# hifi.net
KiCad netlist of a schematic drawn in EAGLE
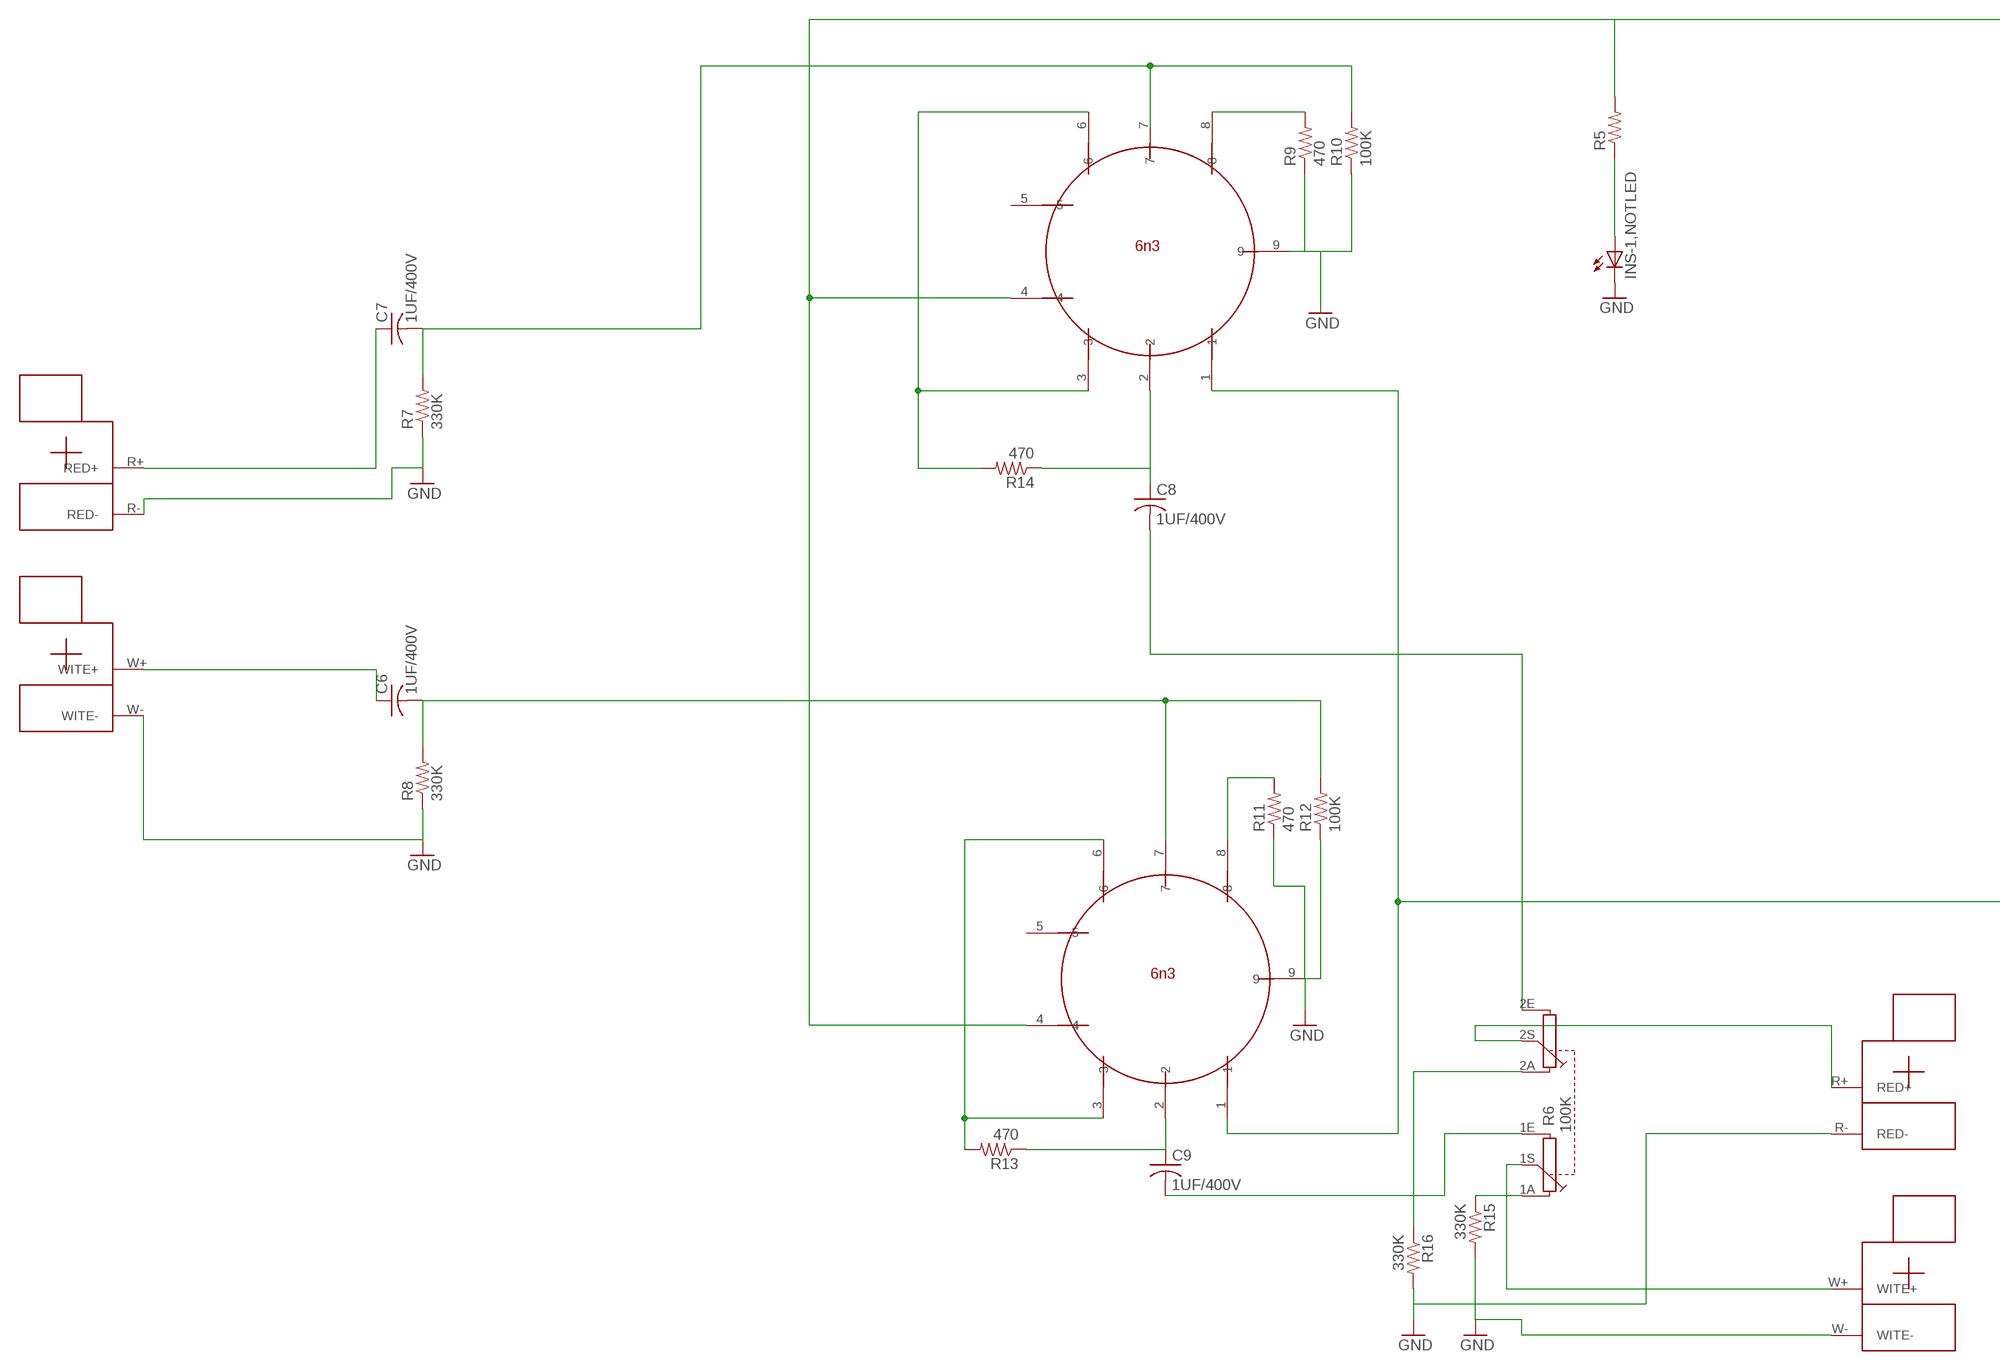
[diagram p0: schematic, sheet 1, part 1 of 2]
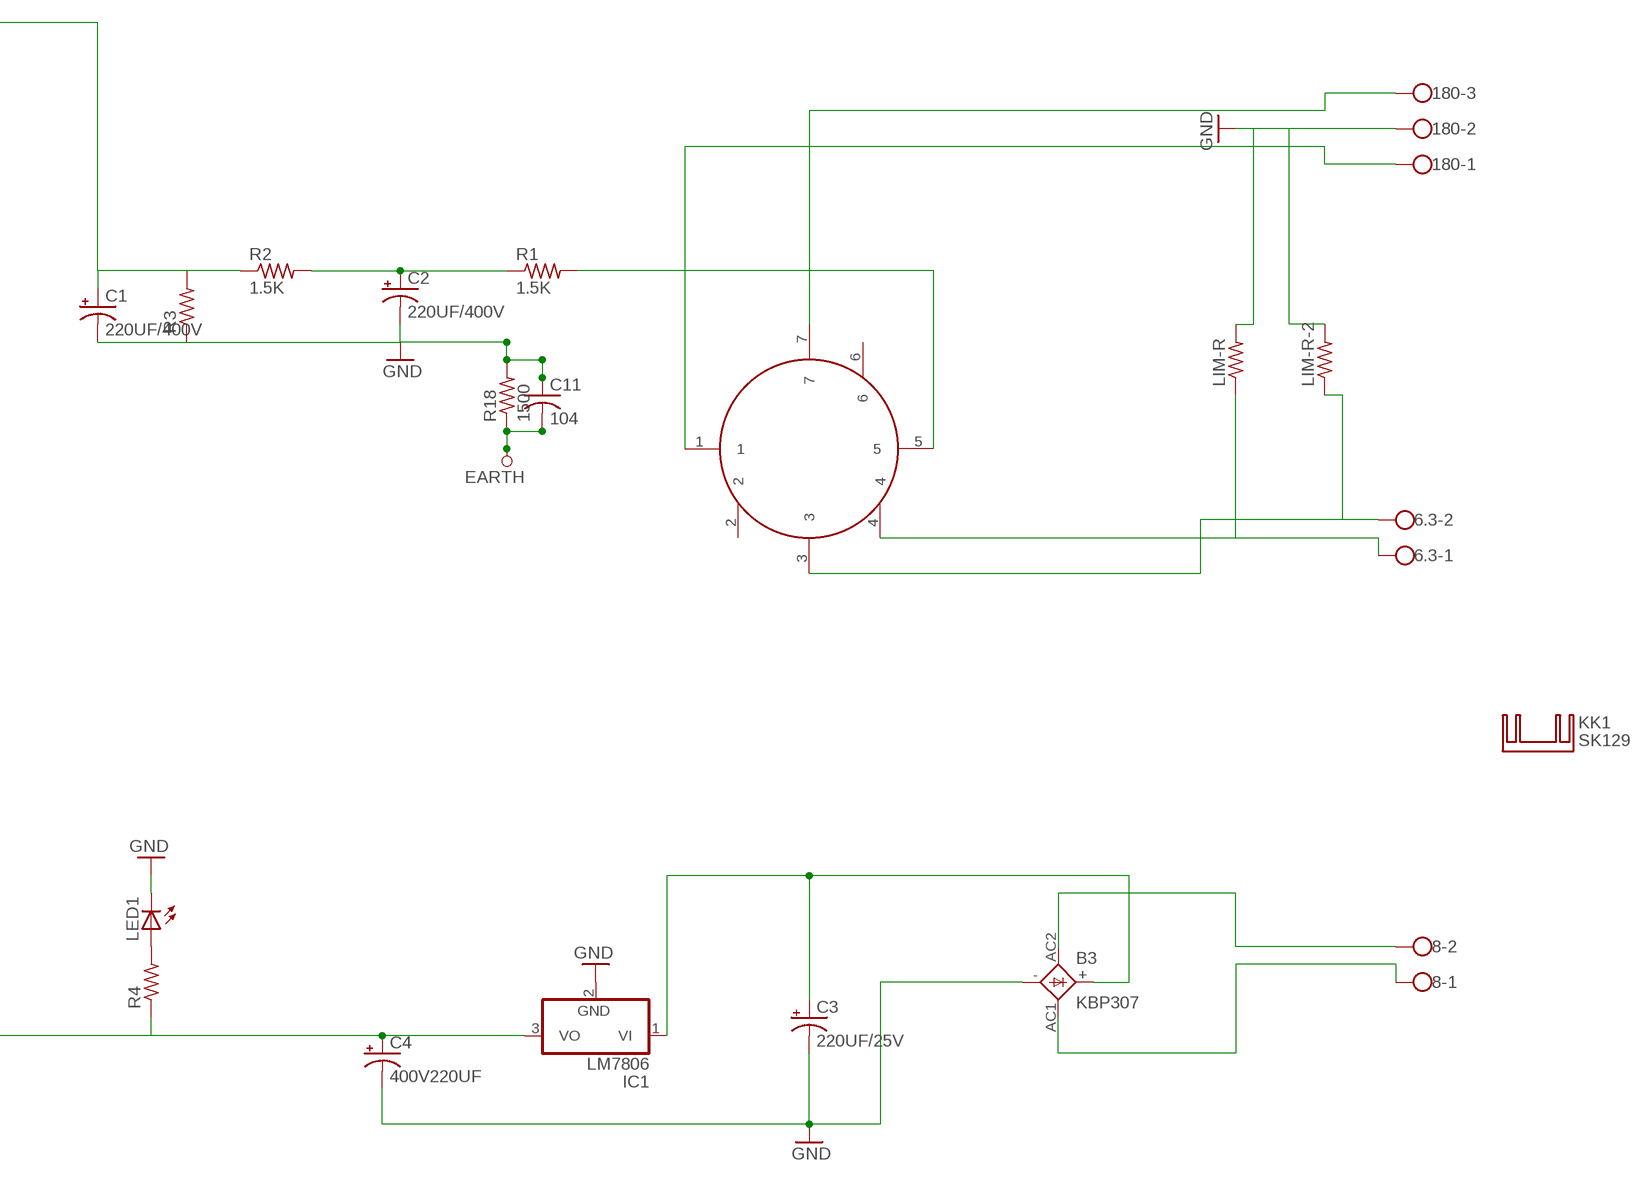
[diagram p1: schematic, sheet 1, part 2 of 2]

(export (version "E")
  (design (tool "Eeschema 10.0.6"))
  (components
    (comp (ref "6.3")
      (value "W237-102")
      (footprint "eagle-import:W237-102")
      (fields (field (name "MPN") "237-102"))
      (libsource (lib "eagle-import") (part "W237-102"))
    )
    (comp (ref "8")
      (value "W237-102")
      (footprint "eagle-import:W237-102")
      (fields (field (name "MPN") "237-102"))
      (libsource (lib "eagle-import") (part "W237-102"))
    )
    (comp (ref "180")
      (value "W237-103")
      (footprint "eagle-import:W237-103")
      (fields (field (name "MPN") "237-103"))
      (libsource (lib "eagle-import") (part "W237-103"))
    )
    (comp (ref "B3")
      (value "KBP307")
      (footprint "eagle-import:KBL")
      (libsource (lib "eagle-import") (part "KBL"))
    )
    (comp (ref "C1")
      (value "220UF/400V")
      (footprint "eagle-import:EB35D")
      (libsource (lib "eagle-import") (part "CPOL-USE10-35"))
    )
    (comp (ref "C2")
      (value "220UF/400V")
      (footprint "eagle-import:EB35D")
      (libsource (lib "eagle-import") (part "CPOL-USE10-35"))
    )
    (comp (ref "C3")
      (value "220UF/25V")
      (footprint "eagle-import:E3,5-10")
      (libsource (lib "eagle-import") (part "CPOL-USE3.5-10"))
    )
    (comp (ref "C4")
      (value "400V220UF")
      (footprint "eagle-import:EB30D")
      (libsource (lib "eagle-import") (part "CPOL-USE10-30"))
    )
    (comp (ref "C6")
      (value "1UF/400V")
      (footprint "eagle-import:C375-192X418")
      (libsource (lib "eagle-import") (part "C-US375-192X418"))
    )
    (comp (ref "C7")
      (value "1UF/400V")
      (footprint "eagle-import:C375-192X418")
      (libsource (lib "eagle-import") (part "C-US375-192X418"))
    )
    (comp (ref "C8")
      (value "1UF/400V")
      (footprint "eagle-import:C375-192X418")
      (libsource (lib "eagle-import") (part "C-US375-192X418"))
    )
    (comp (ref "C9")
      (value "1UF/400V")
      (footprint "eagle-import:C375-192X418")
      (libsource (lib "eagle-import") (part "C-US375-192X418"))
    )
    (comp (ref "C11")
      (value "104")
      (footprint "eagle-import:C075-052X106")
      (libsource (lib "eagle-import") (part "C-US075-052X106"))
    )
    (comp (ref "EARTH")
      (value "PAD_TERMINAL-4.1MMROUND")
      (footprint "eagle-import:PAD_ROUND_4.1MM")
      (libsource (lib "eagle-import") (part "PAD_TERMINAL-4.1MMROUND"))
    )
    (comp (ref "IC1")
      (value "LM7806")
      (footprint "eagle-import:TO220V")
      (libsource (lib "eagle-import") (part "78TV05"))
    )
    (comp (ref "INS-1,NOTLED")
      (value "LED5MM")
      (footprint "eagle-import:LED5MM")
      (libsource (lib "eagle-import") (part "LED5MM"))
    )
    (comp (ref "KK1")
      (value "SK129")
      (footprint "eagle-import:SK129-HOLE")
      (libsource (lib "eagle-import") (part "SK129"))
    )
    (comp (ref "LED1")
      (value "LED5MM")
      (footprint "eagle-import:LED5MM")
      (libsource (lib "eagle-import") (part "LED5MM"))
    )
    (comp (ref "LIM-R")
      (value "R-US_0207/10")
      (footprint "eagle-import:0207_10")
      (libsource (lib "eagle-import") (part "R-US_0207/10"))
    )
    (comp (ref "LIM-R-2")
      (value "R-US_0207/10")
      (footprint "eagle-import:0207_10")
      (libsource (lib "eagle-import") (part "R-US_0207/10"))
    )
    (comp (ref "R1")
      (value "1.5K")
      (footprint "eagle-import:0309_12")
      (libsource (lib "eagle-import") (part "R-US_0309/12"))
    )
    (comp (ref "R2")
      (value "1.5K")
      (footprint "eagle-import:0309_12")
      (libsource (lib "eagle-import") (part "R-US_0309/12"))
    )
    (comp (ref "R3")
      (value "R-US_0309/12")
      (footprint "eagle-import:0309_12")
      (libsource (lib "eagle-import") (part "R-US_0309/12"))
    )
    (comp (ref "R4")
      (value "R-US_0207/10")
      (footprint "eagle-import:0207_10")
      (libsource (lib "eagle-import") (part "R-US_0207/10"))
    )
    (comp (ref "R5")
      (value "R-US_0309/12")
      (footprint "eagle-import:0309_12")
      (libsource (lib "eagle-import") (part "R-US_0309/12"))
    )
    (comp (ref "R6")
      (value "100K")
      (footprint "eagle-import:PC16D")
      (libsource (lib "eagle-import") (part "PC16D"))
    )
    (comp (ref "R7")
      (value "330K")
      (footprint "eagle-import:0207_10")
      (libsource (lib "eagle-import") (part "R-US_0207/10"))
    )
    (comp (ref "R8")
      (value "330K")
      (footprint "eagle-import:0207_10")
      (libsource (lib "eagle-import") (part "R-US_0207/10"))
    )
    (comp (ref "R9")
      (value "470")
      (footprint "eagle-import:0207_10")
      (libsource (lib "eagle-import") (part "R-US_0207/10"))
    )
    (comp (ref "R10")
      (value "100K")
      (footprint "eagle-import:0207_10")
      (libsource (lib "eagle-import") (part "R-US_0207/10"))
    )
    (comp (ref "R11")
      (value "470")
      (footprint "eagle-import:0207_10")
      (libsource (lib "eagle-import") (part "R-US_0207/10"))
    )
    (comp (ref "R12")
      (value "100K")
      (footprint "eagle-import:0207_10")
      (libsource (lib "eagle-import") (part "R-US_0207/10"))
    )
    (comp (ref "R13")
      (value "470")
      (footprint "eagle-import:0207_10")
      (libsource (lib "eagle-import") (part "R-US_0207/10"))
    )
    (comp (ref "R14")
      (value "470")
      (footprint "eagle-import:0207_10")
      (libsource (lib "eagle-import") (part "R-US_0207/10"))
    )
    (comp (ref "R15")
      (value "330K")
      (footprint "eagle-import:0207_10")
      (libsource (lib "eagle-import") (part "R-US_0207/10"))
    )
    (comp (ref "R16")
      (value "330K")
      (footprint "eagle-import:0207_10")
      (libsource (lib "eagle-import") (part "R-US_0207/10"))
    )
    (comp (ref "R18")
      (value "1500")
      (footprint "eagle-import:0309_12")
      (libsource (lib "eagle-import") (part "R-US_0309/12"))
    )
    (comp (ref "U$1")
      (value "6Z4-SIMPLE")
      (footprint "eagle-import:MINI_P7")
      (libsource (lib "eagle-import") (part "6Z4-SIMPLE"))
    )
    (comp (ref "U$2")
      (value "6N3-SIMPLE")
      (footprint "eagle-import:NOVAL")
      (libsource (lib "eagle-import") (part "6N3-SIMPLE"))
    )
    (comp (ref "U$3")
      (value "6N3-SIMPLE")
      (footprint "eagle-import:NOVAL")
      (libsource (lib "eagle-import") (part "6N3-SIMPLE"))
    )
    (comp (ref "U$4")
      (value "RCANEW")
      (footprint "eagle-import:RCA")
      (libsource (lib "eagle-import") (part "RCANEW"))
    )
    (comp (ref "U$5")
      (value "RCANEW")
      (footprint "eagle-import:RCA")
      (libsource (lib "eagle-import") (part "RCANEW"))
    )
  )
  (nets
    (net (code "1") (name "GND") (class "Default")
      (node (ref "180") (pin "2") (pinfunction "KL_2") (pintype "passive"))
      (node (ref "B3") (pin "-") (pinfunction "-_-") (pintype "passive"))
      (node (ref "C1") (pin "-") (pinfunction "-_-") (pintype "passive"))
      (node (ref "C11") (pin "1") (pinfunction "1_1") (pintype "passive"))
      (node (ref "C2") (pin "-") (pinfunction "-_-") (pintype "passive"))
      (node (ref "C3") (pin "-") (pinfunction "-_-") (pintype "passive"))
      (node (ref "C4") (pin "-") (pinfunction "-_-") (pintype "passive"))
      (node (ref "IC1") (pin "2") (pinfunction "GND_2") (pintype "passive"))
      (node (ref "INS-1,NOTLED") (pin "K") (pinfunction "C_K") (pintype "passive"))
      (node (ref "LED1") (pin "K") (pinfunction "C_K") (pintype "passive"))
      (node (ref "LIM-R") (pin "2") (pinfunction "2_2") (pintype "passive"))
      (node (ref "LIM-R-2") (pin "2") (pinfunction "2_2") (pintype "passive"))
      (node (ref "R11") (pin "1") (pinfunction "1_1") (pintype "passive"))
      (node (ref "R12") (pin "1") (pinfunction "1_1") (pintype "passive"))
      (node (ref "R15") (pin "2") (pinfunction "2_2") (pintype "passive"))
      (node (ref "R16") (pin "2") (pinfunction "2_2") (pintype "passive"))
      (node (ref "R18") (pin "2") (pinfunction "2_2") (pintype "passive"))
      (node (ref "R3") (pin "1") (pinfunction "1_1") (pintype "passive"))
      (node (ref "R7") (pin "1") (pinfunction "1_1") (pintype "passive"))
      (node (ref "R8") (pin "1") (pinfunction "1_1") (pintype "passive"))
      (node (ref "U$3") (pin "9") (pinfunction "9_9") (pintype "bidirectional"))
      (node (ref "U$4") (pin "R-") (pinfunction "RED-_R-") (pintype "bidirectional"))
      (node (ref "U$4") (pin "W-") (pinfunction "WITE-_W-") (pintype "bidirectional"))
      (node (ref "U$5") (pin "R-") (pinfunction "RED-_R-") (pintype "bidirectional"))
      (node (ref "U$5") (pin "W-") (pinfunction "WITE-_W-") (pintype "bidirectional"))
    )
    (net (code "2") (name "Net-(6.3A-KL)") (class "Default")
      (node (ref "6.3") (pin "1") (pinfunction "KL_1") (pintype "passive"))
      (node (ref "LIM-R") (pin "1") (pinfunction "1_1") (pintype "passive"))
      (node (ref "U$1") (pin "4") (pinfunction "4_4") (pintype "bidirectional"))
    )
    (net (code "3") (name "Net-(6.3B-KL)") (class "Default")
      (node (ref "6.3") (pin "2") (pinfunction "KL_2") (pintype "passive"))
      (node (ref "LIM-R-2") (pin "1") (pinfunction "1_1") (pintype "passive"))
      (node (ref "U$1") (pin "3") (pinfunction "3_3") (pintype "bidirectional"))
    )
    (net (code "4") (name "Net-(8A-KL)") (class "Default")
      (node (ref "8") (pin "1") (pinfunction "KL_1") (pintype "passive"))
      (node (ref "B3") (pin "AC1") (pinfunction "AC2_AC1") (pintype "passive"))
    )
    (net (code "5") (name "Net-(8B-KL)") (class "Default")
      (node (ref "8") (pin "2") (pinfunction "KL_2") (pintype "passive"))
      (node (ref "B3") (pin "AC2") (pinfunction "AC1_AC2") (pintype "passive"))
    )
    (net (code "6") (name "Net-(180A-KL)") (class "Default")
      (node (ref "180") (pin "1") (pinfunction "KL_1") (pintype "passive"))
      (node (ref "U$1") (pin "1") (pinfunction "1_1") (pintype "bidirectional"))
    )
    (net (code "7") (name "Net-(180C-KL)") (class "Default")
      (node (ref "180") (pin "3") (pinfunction "KL_3") (pintype "passive"))
      (node (ref "U$1") (pin "7") (pinfunction "7_7") (pintype "bidirectional"))
    )
    (net (code "8") (name "Net-(C1-Pad+)") (class "Default")
      (node (ref "C1") (pin "+") (pinfunction "+_+") (pintype "passive"))
      (node (ref "R2") (pin "1") (pinfunction "1_1") (pintype "passive"))
      (node (ref "R3") (pin "2") (pinfunction "2_2") (pintype "passive"))
      (node (ref "R5") (pin "2") (pinfunction "2_2") (pintype "passive"))
      (node (ref "U$2") (pin "4") (pinfunction "4_4") (pintype "bidirectional"))
      (node (ref "U$3") (pin "4") (pinfunction "4_4") (pintype "bidirectional"))
    )
    (net (code "9") (name "Net-(C2-Pad+)") (class "Default")
      (node (ref "C2") (pin "+") (pinfunction "+_+") (pintype "passive"))
      (node (ref "R1") (pin "1") (pinfunction "1_1") (pintype "passive"))
      (node (ref "R2") (pin "2") (pinfunction "2_2") (pintype "passive"))
    )
    (net (code "10") (name "Net-(C6-Pad2)") (class "Default")
      (node (ref "C6") (pin "2") (pinfunction "2_2") (pintype "passive"))
      (node (ref "R12") (pin "2") (pinfunction "2_2") (pintype "passive"))
      (node (ref "R8") (pin "2") (pinfunction "2_2") (pintype "passive"))
      (node (ref "U$3") (pin "7") (pinfunction "7_7") (pintype "bidirectional"))
    )
    (net (code "11") (name "Net-(C7-Pad2)") (class "Default")
      (node (ref "C7") (pin "2") (pinfunction "2_2") (pintype "passive"))
      (node (ref "R10") (pin "2") (pinfunction "2_2") (pintype "passive"))
      (node (ref "R7") (pin "2") (pinfunction "2_2") (pintype "passive"))
    )
    (net (code "12") (name "Net-(C8-Pad1)") (class "Default")
      (node (ref "C8") (pin "1") (pinfunction "1_1") (pintype "passive"))
      (node (ref "R14") (pin "1") (pinfunction "1_1") (pintype "passive"))
      (node (ref "U$2") (pin "2") (pinfunction "2_2") (pintype "bidirectional"))
    )
    (net (code "13") (name "Net-(C8-Pad2)") (class "Default")
      (node (ref "C8") (pin "2") (pinfunction "2_2") (pintype "passive"))
      (node (ref "R6") (pin "2E") (pinfunction "2E_2E") (pintype "passive"))
    )
    (net (code "14") (name "Net-(C9-Pad1)") (class "Default")
      (node (ref "C9") (pin "1") (pinfunction "1_1") (pintype "passive"))
      (node (ref "R13") (pin "1") (pinfunction "1_1") (pintype "passive"))
      (node (ref "U$3") (pin "2") (pinfunction "2_2") (pintype "bidirectional"))
    )
    (net (code "15") (name "Net-(C9-Pad2)") (class "Default")
      (node (ref "C9") (pin "2") (pinfunction "2_2") (pintype "passive"))
      (node (ref "R6") (pin "1E") (pinfunction "1E_1E") (pintype "passive"))
    )
    (net (code "16") (name "Net-(C11-Pad2)") (class "Default")
      (node (ref "C11") (pin "2") (pinfunction "2_2") (pintype "passive"))
      (node (ref "EARTH") (pin "P") (pinfunction "P_P") (pintype "passive"))
      (node (ref "R18") (pin "1") (pinfunction "1_1") (pintype "passive"))
    )
    (net (code "17") (name "Net-(IC1-VI)") (class "Default")
      (node (ref "B3") (pin "+") (pinfunction "+_+") (pintype "passive"))
      (node (ref "C3") (pin "+") (pinfunction "+_+") (pintype "passive"))
      (node (ref "IC1") (pin "1") (pinfunction "VI_1") (pintype "input"))
    )
    (net (code "18") (name "Net-(IC1-VO)") (class "Default")
      (node (ref "C4") (pin "+") (pinfunction "+_+") (pintype "passive"))
      (node (ref "IC1") (pin "3") (pinfunction "VO_3") (pintype "passive"))
      (node (ref "R4") (pin "1") (pinfunction "1_1") (pintype "passive"))
      (node (ref "U$2") (pin "1") (pinfunction "1_1") (pintype "bidirectional"))
      (node (ref "U$3") (pin "1") (pinfunction "1_1") (pintype "bidirectional"))
    )
    (net (code "19") (name "Net-(INS-1,NOTLED-PadA)") (class "Default")
      (node (ref "INS-1,NOTLED") (pin "A") (pinfunction "A_A") (pintype "passive"))
      (node (ref "R5") (pin "1") (pinfunction "1_1") (pintype "passive"))
    )
    (net (code "20") (name "Net-(LED1-PadA)") (class "Default")
      (node (ref "LED1") (pin "A") (pinfunction "A_A") (pintype "passive"))
      (node (ref "R4") (pin "2") (pinfunction "2_2") (pintype "passive"))
    )
    (net (code "21") (name "Net-(R1-Pad2)") (class "Default")
      (node (ref "R1") (pin "2") (pinfunction "2_2") (pintype "passive"))
      (node (ref "U$1") (pin "5") (pinfunction "5_5") (pintype "bidirectional"))
    )
    (net (code "22") (name "Net-(R9-Pad2)") (class "Default")
      (node (ref "R9") (pin "2") (pinfunction "2_2") (pintype "passive"))
      (node (ref "U$2") (pin "8") (pinfunction "8_8") (pintype "bidirectional"))
    )
    (net (code "23") (name "Net-(R10-Pad1)") (class "Default")
      (node (ref "R10") (pin "1") (pinfunction "1_1") (pintype "passive"))
      (node (ref "R9") (pin "1") (pinfunction "1_1") (pintype "passive"))
      (node (ref "U$2") (pin "9") (pinfunction "9_9") (pintype "bidirectional"))
    )
    (net (code "24") (name "Net-(R11-Pad2)") (class "Default")
      (node (ref "R11") (pin "2") (pinfunction "2_2") (pintype "passive"))
      (node (ref "U$3") (pin "8") (pinfunction "8_8") (pintype "bidirectional"))
    )
    (net (code "25") (name "Net-(R13-Pad2)") (class "Default")
      (node (ref "R13") (pin "2") (pinfunction "2_2") (pintype "passive"))
      (node (ref "U$3") (pin "3") (pinfunction "3_3") (pintype "bidirectional"))
      (node (ref "U$3") (pin "6") (pinfunction "6_6") (pintype "bidirectional"))
    )
    (net (code "26") (name "Net-(R14-Pad2)") (class "Default")
      (node (ref "R14") (pin "2") (pinfunction "2_2") (pintype "passive"))
      (node (ref "U$2") (pin "3") (pinfunction "3_3") (pintype "bidirectional"))
      (node (ref "U$2") (pin "6") (pinfunction "6_6") (pintype "bidirectional"))
    )
    (net (code "27") (name "Net-(R15-Pad1)") (class "Default")
      (node (ref "R15") (pin "1") (pinfunction "1_1") (pintype "passive"))
      (node (ref "R6") (pin "1A") (pinfunction "1A_1A") (pintype "passive"))
    )
    (net (code "28") (name "Net-(R16-Pad1)") (class "Default")
      (node (ref "R16") (pin "1") (pinfunction "1_1") (pintype "passive"))
      (node (ref "R6") (pin "2A") (pinfunction "2A_2A") (pintype "passive"))
    )
    (net (code "29") (name "Net-(U$4-RED+)") (class "Default")
      (node (ref "C7") (pin "1") (pinfunction "1_1") (pintype "passive"))
      (node (ref "U$4") (pin "R+") (pinfunction "RED+_R+") (pintype "bidirectional"))
    )
    (net (code "30") (name "Net-(U$4-WITE+)") (class "Default")
      (node (ref "C6") (pin "1") (pinfunction "1_1") (pintype "passive"))
      (node (ref "U$4") (pin "W+") (pinfunction "WITE+_W+") (pintype "bidirectional"))
    )
    (net (code "31") (name "Net-(U$5-RED+)") (class "Default")
      (node (ref "R6") (pin "2S") (pinfunction "2S_2S") (pintype "passive"))
      (node (ref "U$5") (pin "R+") (pinfunction "RED+_R+") (pintype "bidirectional"))
    )
    (net (code "32") (name "Net-(U$5-WITE+)") (class "Default")
      (node (ref "R6") (pin "1S") (pinfunction "1S_1S") (pintype "passive"))
      (node (ref "U$5") (pin "W+") (pinfunction "WITE+_W+") (pintype "bidirectional"))
    )
    (net (code "33") (name "unconnected-(U$1-Pad2)") (class "Default")
      (node (ref "U$1") (pin "2") (pinfunction "2_2") (pintype "bidirectional"))
    )
    (net (code "34") (name "unconnected-(U$1-Pad6)") (class "Default")
      (node (ref "U$1") (pin "6") (pinfunction "6_6") (pintype "bidirectional"))
    )
    (net (code "35") (name "unconnected-(U$2-Pad5)") (class "Default")
      (node (ref "U$2") (pin "5") (pinfunction "5_5") (pintype "bidirectional"))
    )
    (net (code "36") (name "unconnected-(U$2-Pad7)") (class "Default")
      (node (ref "U$2") (pin "7") (pinfunction "7_7") (pintype "bidirectional"))
    )
    (net (code "37") (name "unconnected-(U$3-Pad5)") (class "Default")
      (node (ref "U$3") (pin "5") (pinfunction "5_5") (pintype "bidirectional"))
    )
  )
)
